# control.net
KiCad netlist of a schematic drawn in EAGLE
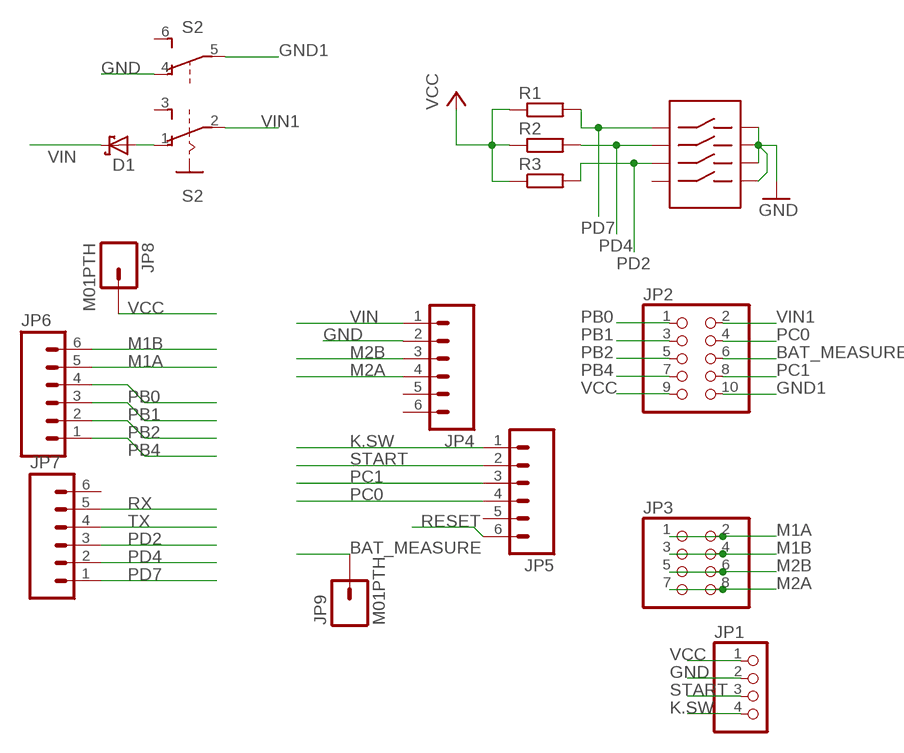
[diagram p0: schematic, sheet 1]

(export (version "E")
  (design (tool "Eeschema 10.0.6"))
  (components
    (comp (ref "D1")
      (value "SCHOTTKY-DIODESMC")
      (footprint "eagle-import:SMC")
      (libsource (lib "eagle-import") (part "SCHOTTKY-DIODESMC"))
    )
    (comp (ref "JP1")
      (value "PINHD-1X4")
      (footprint "eagle-import:1X04")
      (libsource (lib "eagle-import") (part "PINHD-1X4"))
    )
    (comp (ref "JP2")
      (value "PINHD-2X5")
      (footprint "eagle-import:2X05")
      (libsource (lib "eagle-import") (part "PINHD-2X5"))
    )
    (comp (ref "JP3")
      (value "PINHD-2X4")
      (footprint "eagle-import:2X04")
      (libsource (lib "eagle-import") (part "PINHD-2X4"))
    )
    (comp (ref "JP4")
      (value "M06SMD-STRAIGHT")
      (footprint "eagle-import:1X06_SMD_STRAIGHT")
      (libsource (lib "eagle-import") (part "M06SMD-STRAIGHT"))
    )
    (comp (ref "JP5")
      (value "M06SMD-STRAIGHT")
      (footprint "eagle-import:1X06_SMD_STRAIGHT")
      (libsource (lib "eagle-import") (part "M06SMD-STRAIGHT"))
    )
    (comp (ref "JP6")
      (value "M06SMD-STRAIGHT")
      (footprint "eagle-import:1X06_SMD_STRAIGHT")
      (libsource (lib "eagle-import") (part "M06SMD-STRAIGHT"))
    )
    (comp (ref "JP7")
      (value "M06SMD-STRAIGHT")
      (footprint "eagle-import:1X06_SMD_STRAIGHT")
      (libsource (lib "eagle-import") (part "M06SMD-STRAIGHT"))
    )
    (comp (ref "JP8")
      (value "M01PTH")
      (footprint "eagle-import:1X01")
      (libsource (lib "eagle-import") (part "M01PTH"))
    )
    (comp (ref "JP9")
      (value "M01PTH")
      (footprint "eagle-import:1X01")
      (libsource (lib "eagle-import") (part "M01PTH"))
    )
    (comp (ref "R1")
      (value "R-EU_R0805")
      (footprint "eagle-import:R0805")
      (libsource (lib "eagle-import") (part "R-EU_R0805"))
    )
    (comp (ref "R2")
      (value "R-EU_R0805")
      (footprint "eagle-import:R0805")
      (libsource (lib "eagle-import") (part "R-EU_R0805"))
    )
    (comp (ref "R3")
      (value "R-EU_R0805")
      (footprint "eagle-import:R0805")
      (libsource (lib "eagle-import") (part "R-EU_R0805"))
    )
    (comp (ref "S2")
      (value "A68-A31")
      (footprint "eagle-import:A68-A31")
      (libsource (lib "eagle-import") (part "A68-A31"))
    )
    (comp (ref "U$2")
      (value "DGH04")
      (footprint "eagle-import:GDH04")
      (libsource (lib "eagle-import") (part "DGH04"))
    )
  )
  (nets
    (net (code "1") (name "/BAT_MEASURE") (class "Default")
      (node (ref "JP2") (pin "6") (pinfunction "6_6") (pintype "passive"))
      (node (ref "JP9") (pin "1") (pinfunction "1_1") (pintype "passive"))
    )
    (net (code "2") (name "/GND1") (class "Default")
      (node (ref "JP2") (pin "10") (pinfunction "10_10") (pintype "passive"))
      (node (ref "S2") (pin "5") (pinfunction "P_5") (pintype "passive"))
    )
    (net (code "3") (name "/K.SW") (class "Default")
      (node (ref "JP1") (pin "4") (pinfunction "4_4") (pintype "passive"))
      (node (ref "JP5") (pin "1") (pinfunction "1_1") (pintype "passive"))
    )
    (net (code "4") (name "/M1A") (class "Default")
      (node (ref "JP3") (pin "1") (pinfunction "1_1") (pintype "passive"))
      (node (ref "JP3") (pin "2") (pinfunction "2_2") (pintype "passive"))
      (node (ref "JP6") (pin "5") (pinfunction "5_5") (pintype "passive"))
    )
    (net (code "5") (name "/M1B") (class "Default")
      (node (ref "JP3") (pin "3") (pinfunction "3_3") (pintype "passive"))
      (node (ref "JP3") (pin "4") (pinfunction "4_4") (pintype "passive"))
      (node (ref "JP6") (pin "6") (pinfunction "6_6") (pintype "passive"))
    )
    (net (code "6") (name "/M2A") (class "Default")
      (node (ref "JP3") (pin "7") (pinfunction "7_7") (pintype "passive"))
      (node (ref "JP3") (pin "8") (pinfunction "8_8") (pintype "passive"))
      (node (ref "JP4") (pin "4") (pinfunction "4_4") (pintype "passive"))
    )
    (net (code "7") (name "/M2B") (class "Default")
      (node (ref "JP3") (pin "5") (pinfunction "5_5") (pintype "passive"))
      (node (ref "JP3") (pin "6") (pinfunction "6_6") (pintype "passive"))
      (node (ref "JP4") (pin "3") (pinfunction "3_3") (pintype "passive"))
    )
    (net (code "8") (name "/PB0") (class "Default")
      (node (ref "JP2") (pin "1") (pinfunction "1_1") (pintype "passive"))
      (node (ref "JP6") (pin "4") (pinfunction "4_4") (pintype "passive"))
    )
    (net (code "9") (name "/PB1") (class "Default")
      (node (ref "JP2") (pin "3") (pinfunction "3_3") (pintype "passive"))
      (node (ref "JP6") (pin "3") (pinfunction "3_3") (pintype "passive"))
    )
    (net (code "10") (name "/PB2") (class "Default")
      (node (ref "JP2") (pin "5") (pinfunction "5_5") (pintype "passive"))
      (node (ref "JP6") (pin "2") (pinfunction "2_2") (pintype "passive"))
    )
    (net (code "11") (name "/PB4") (class "Default")
      (node (ref "JP2") (pin "7") (pinfunction "7_7") (pintype "passive"))
      (node (ref "JP6") (pin "1") (pinfunction "1_1") (pintype "passive"))
    )
    (net (code "12") (name "/PC0") (class "Default")
      (node (ref "JP2") (pin "4") (pinfunction "4_4") (pintype "passive"))
      (node (ref "JP5") (pin "4") (pinfunction "4_4") (pintype "passive"))
    )
    (net (code "13") (name "/PC1") (class "Default")
      (node (ref "JP2") (pin "8") (pinfunction "8_8") (pintype "passive"))
      (node (ref "JP5") (pin "3") (pinfunction "3_3") (pintype "passive"))
    )
    (net (code "14") (name "/PD2") (class "Default")
      (node (ref "JP7") (pin "3") (pinfunction "3_3") (pintype "passive"))
      (node (ref "R3") (pin "2") (pinfunction "2_2") (pintype "passive"))
      (node (ref "U$2") (pin "P$4") (pinfunction "P$3_P$4") (pintype "bidirectional"))
    )
    (net (code "15") (name "/PD4") (class "Default")
      (node (ref "JP7") (pin "2") (pinfunction "2_2") (pintype "passive"))
      (node (ref "R2") (pin "2") (pinfunction "2_2") (pintype "passive"))
      (node (ref "U$2") (pin "P$3") (pinfunction "P$2_P$3") (pintype "bidirectional"))
    )
    (net (code "16") (name "/PD7") (class "Default")
      (node (ref "JP7") (pin "1") (pinfunction "1_1") (pintype "passive"))
      (node (ref "R1") (pin "2") (pinfunction "2_2") (pintype "passive"))
      (node (ref "U$2") (pin "P$2") (pinfunction "P$1_P$2") (pintype "bidirectional"))
    )
    (net (code "17") (name "/RESET") (class "Default")
      (node (ref "JP5") (pin "6") (pinfunction "6_6") (pintype "passive"))
    )
    (net (code "18") (name "/RX") (class "Default")
      (node (ref "JP7") (pin "5") (pinfunction "5_5") (pintype "passive"))
    )
    (net (code "19") (name "/START") (class "Default")
      (node (ref "JP1") (pin "3") (pinfunction "3_3") (pintype "passive"))
      (node (ref "JP5") (pin "2") (pinfunction "2_2") (pintype "passive"))
    )
    (net (code "20") (name "/TX") (class "Default")
      (node (ref "JP7") (pin "4") (pinfunction "4_4") (pintype "passive"))
    )
    (net (code "21") (name "/VIN") (class "Default")
      (node (ref "D1") (pin "C") (pinfunction "C_C") (pintype "passive"))
      (node (ref "JP4") (pin "1") (pinfunction "1_1") (pintype "passive"))
    )
    (net (code "22") (name "/VIN1") (class "Default")
      (node (ref "JP2") (pin "2") (pinfunction "2_2") (pintype "passive"))
      (node (ref "S2") (pin "2") (pinfunction "P_2") (pintype "passive"))
    )
    (net (code "23") (name "GND") (class "Default")
      (node (ref "JP1") (pin "2") (pinfunction "2_2") (pintype "passive"))
      (node (ref "JP4") (pin "2") (pinfunction "2_2") (pintype "passive"))
      (node (ref "S2") (pin "4") (pinfunction "O_4") (pintype "passive"))
      (node (ref "U$2") (pin "P$1") (pinfunction "P$5_P$1") (pintype "bidirectional"))
      (node (ref "U$2") (pin "P$6") (pinfunction "P$6_P$6") (pintype "bidirectional"))
      (node (ref "U$2") (pin "P$7") (pinfunction "P$7_P$7") (pintype "bidirectional"))
      (node (ref "U$2") (pin "P$8") (pinfunction "P$8_P$8") (pintype "bidirectional"))
    )
    (net (code "24") (name "Net-(S2A-O)") (class "Default")
      (node (ref "D1") (pin "A") (pinfunction "A_A") (pintype "passive"))
      (node (ref "S2") (pin "1") (pinfunction "O_1") (pintype "passive"))
    )
    (net (code "25") (name "VCC") (class "Default")
      (node (ref "JP1") (pin "1") (pinfunction "1_1") (pintype "passive"))
      (node (ref "JP2") (pin "9") (pinfunction "9_9") (pintype "passive"))
      (node (ref "JP8") (pin "1") (pinfunction "1_1") (pintype "passive"))
      (node (ref "R1") (pin "1") (pinfunction "1_1") (pintype "passive"))
      (node (ref "R2") (pin "1") (pinfunction "1_1") (pintype "passive"))
      (node (ref "R3") (pin "1") (pinfunction "1_1") (pintype "passive"))
    )
    (net (code "26") (name "unconnected-(JP4-Pad5)") (class "Default")
      (node (ref "JP4") (pin "5") (pinfunction "5_5") (pintype "passive"))
    )
    (net (code "27") (name "unconnected-(JP4-Pad6)") (class "Default")
      (node (ref "JP4") (pin "6") (pinfunction "6_6") (pintype "passive"))
    )
    (net (code "28") (name "unconnected-(JP5-Pad5)") (class "Default")
      (node (ref "JP5") (pin "5") (pinfunction "5_5") (pintype "passive"))
    )
    (net (code "29") (name "unconnected-(JP7-Pad6)") (class "Default")
      (node (ref "JP7") (pin "6") (pinfunction "6_6") (pintype "passive"))
    )
    (net (code "30") (name "unconnected-(S2A-S-Pad3)") (class "Default")
      (node (ref "S2") (pin "3") (pinfunction "S_3") (pintype "passive"))
    )
    (net (code "31") (name "unconnected-(S2B-S-Pad6)") (class "Default")
      (node (ref "S2") (pin "6") (pinfunction "S_6") (pintype "passive"))
    )
    (net (code "32") (name "unconnected-(U$2-P$4-PadP$5)") (class "Default")
      (node (ref "U$2") (pin "P$5") (pinfunction "P$4_P$5") (pintype "bidirectional"))
    )
  )
)
